# QuardnoShield_0_1.net
KiCad netlist of a schematic drawn in Altium Designer
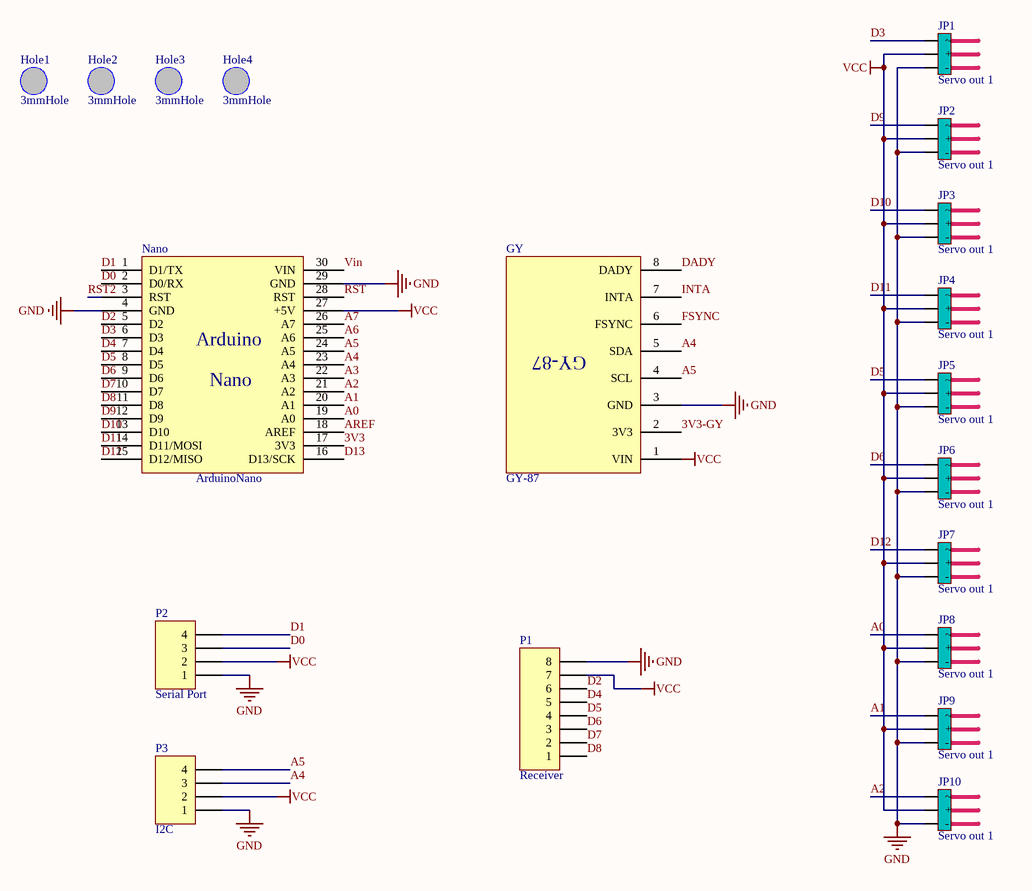
[diagram p0: QuardnoShield_0_1.SchDoc]

(export (version "E")
  (design (tool "Eeschema 10.0.6"))
  (components
    (comp (ref "GY") (value "GY-87") (footprint "GY-87") (libsource (lib "Drone") (part "GY-87")))
    (comp (ref "Hole1")
      (value "3mmHole")
      (footprint "3mmHoleSmall")
      (libsource (lib "Drone") (part "3mmHole"))
    )
    (comp (ref "Hole2")
      (value "3mmHole")
      (footprint "3mmHoleSmall")
      (libsource (lib "Drone") (part "3mmHole"))
    )
    (comp (ref "Hole3")
      (value "3mmHole")
      (footprint "3mmHoleSmall")
      (libsource (lib "Drone") (part "3mmHole"))
    )
    (comp (ref "Hole4")
      (value "3mmHole")
      (footprint "3mmHoleSmall")
      (libsource (lib "Drone") (part "3mmHole"))
    )
    (comp (ref "JP1")
      (value "Servo out 1")
      (footprint "JP")
      (description "Header, 3-Pin, 0.1\"")
      (fields (field (name "MANUFACTURER") "Generic Components"))
      (libsource (lib "Drone") (part "Hdr 3 Pin 0.1"))
    )
    (comp (ref "JP2")
      (value "Servo out 1")
      (footprint "JP")
      (description "Header, 3-Pin, 0.1\"")
      (fields (field (name "MANUFACTURER") "Generic Components"))
      (libsource (lib "Drone") (part "Hdr 3 Pin 0.1"))
    )
    (comp (ref "JP3")
      (value "Servo out 1")
      (footprint "JP")
      (description "Header, 3-Pin, 0.1\"")
      (fields (field (name "MANUFACTURER") "Generic Components"))
      (libsource (lib "Drone") (part "Hdr 3 Pin 0.1"))
    )
    (comp (ref "JP4")
      (value "Servo out 1")
      (footprint "JP")
      (description "Header, 3-Pin, 0.1\"")
      (fields (field (name "MANUFACTURER") "Generic Components"))
      (libsource (lib "Drone") (part "Hdr 3 Pin 0.1"))
    )
    (comp (ref "JP5")
      (value "Servo out 1")
      (footprint "JP")
      (description "Header, 3-Pin, 0.1\"")
      (fields (field (name "MANUFACTURER") "Generic Components"))
      (libsource (lib "Drone") (part "Hdr 3 Pin 0.1"))
    )
    (comp (ref "JP6")
      (value "Servo out 1")
      (footprint "JP")
      (description "Header, 3-Pin, 0.1\"")
      (fields (field (name "MANUFACTURER") "Generic Components"))
      (libsource (lib "Drone") (part "Hdr 3 Pin 0.1"))
    )
    (comp (ref "JP7")
      (value "Servo out 1")
      (footprint "JP")
      (description "Header, 3-Pin, 0.1\"")
      (fields (field (name "MANUFACTURER") "Generic Components"))
      (libsource (lib "Drone") (part "Hdr 3 Pin 0.1"))
    )
    (comp (ref "JP8")
      (value "Servo out 1")
      (footprint "JP")
      (description "Header, 3-Pin, 0.1\"")
      (fields (field (name "MANUFACTURER") "Generic Components"))
      (libsource (lib "Drone") (part "Hdr 3 Pin 0.1"))
    )
    (comp (ref "JP9")
      (value "Servo out 1")
      (footprint "JP")
      (description "Header, 3-Pin, 0.1\"")
      (fields (field (name "MANUFACTURER") "Generic Components"))
      (libsource (lib "Drone") (part "Hdr 3 Pin 0.1"))
    )
    (comp (ref "JP10")
      (value "Servo out 1")
      (footprint "JP")
      (description "Header, 3-Pin, 0.1\"")
      (fields (field (name "MANUFACTURER") "Generic Components"))
      (libsource (lib "Drone") (part "Hdr 3 Pin 0.1"))
    )
    (comp (ref "Nano")
      (value "ArduinoNano")
      (footprint "NanoBase")
      (libsource (lib "Drone") (part "ArduinoNano"))
    )
    (comp (ref "P1")
      (value "Receiver")
      (footprint "HDR1X8")
      (description "Header, 8-Pin")
      (fields (field (name "PUBLISHER") "Altium Limited"))
      (libsource (lib "Miscellaneous Connectors") (part "Header 8"))
    )
    (comp (ref "P2")
      (value "Serial Port")
      (footprint "HDR1X4")
      (description "Header, 4-Pin")
      (fields (field (name "PUBLISHER") "Altium Limited"))
      (libsource (lib "Miscellaneous Connectors") (part "Header 4"))
    )
    (comp (ref "P3")
      (value "I2C")
      (footprint "HDR1X4")
      (description "Header, 4-Pin")
      (fields (field (name "PUBLISHER") "Altium Limited"))
      (libsource (lib "Miscellaneous Connectors") (part "Header 4"))
    )
  )
  (nets
    (net (code "1") (name "/3V3") (class "Default")
      (node (ref "Nano") (pin "17") (pinfunction "3V3_17") (pintype "passive"))
    )
    (net (code "2") (name "/3V3-GY") (class "Default")
      (node (ref "GY") (pin "2") (pinfunction "3V3_2") (pintype "passive"))
    )
    (net (code "3") (name "/A0") (class "Default")
      (node (ref "JP8") (pin "1") (pinfunction "~_1") (pintype "passive"))
      (node (ref "Nano") (pin "19") (pinfunction "A0_19") (pintype "passive"))
    )
    (net (code "4") (name "/A1") (class "Default")
      (node (ref "JP9") (pin "1") (pinfunction "~_1") (pintype "passive"))
      (node (ref "Nano") (pin "20") (pinfunction "A1_20") (pintype "passive"))
    )
    (net (code "5") (name "/A2") (class "Default")
      (node (ref "JP10") (pin "1") (pinfunction "~_1") (pintype "passive"))
      (node (ref "Nano") (pin "21") (pinfunction "A2_21") (pintype "passive"))
    )
    (net (code "6") (name "/A3") (class "Default")
      (node (ref "Nano") (pin "22") (pinfunction "A3_22") (pintype "passive"))
    )
    (net (code "7") (name "/A4") (class "Default")
      (node (ref "GY") (pin "5") (pinfunction "SDA_5") (pintype "passive"))
      (node (ref "Nano") (pin "23") (pinfunction "A4_23") (pintype "passive"))
      (node (ref "P3") (pin "3") (pinfunction "3_3") (pintype "passive"))
    )
    (net (code "8") (name "/A5") (class "Default")
      (node (ref "GY") (pin "4") (pinfunction "SCL_4") (pintype "passive"))
      (node (ref "Nano") (pin "24") (pinfunction "A5_24") (pintype "passive"))
      (node (ref "P3") (pin "4") (pinfunction "4_4") (pintype "passive"))
    )
    (net (code "9") (name "/A6") (class "Default")
      (node (ref "Nano") (pin "25") (pinfunction "A6_25") (pintype "passive"))
    )
    (net (code "10") (name "/A7") (class "Default")
      (node (ref "Nano") (pin "26") (pinfunction "A7_26") (pintype "passive"))
    )
    (net (code "11") (name "/AREF") (class "Default")
      (node (ref "Nano") (pin "18") (pinfunction "AREF_18") (pintype "passive"))
    )
    (net (code "12") (name "/D0") (class "Default")
      (node (ref "Nano") (pin "2") (pinfunction "D0/RX_2") (pintype "passive"))
      (node (ref "P2") (pin "3") (pinfunction "3_3") (pintype "passive"))
    )
    (net (code "13") (name "/D1") (class "Default")
      (node (ref "Nano") (pin "1") (pinfunction "D1/TX_1") (pintype "passive"))
      (node (ref "P2") (pin "4") (pinfunction "4_4") (pintype "passive"))
    )
    (net (code "14") (name "/D2") (class "Default")
      (node (ref "Nano") (pin "5") (pinfunction "D2_5") (pintype "passive"))
      (node (ref "P1") (pin "6") (pinfunction "6_6") (pintype "passive"))
    )
    (net (code "15") (name "/D3") (class "Default")
      (node (ref "JP1") (pin "1") (pinfunction "~_1") (pintype "passive"))
      (node (ref "Nano") (pin "6") (pinfunction "D3_6") (pintype "passive"))
    )
    (net (code "16") (name "/D4") (class "Default")
      (node (ref "Nano") (pin "7") (pinfunction "D4_7") (pintype "passive"))
      (node (ref "P1") (pin "5") (pinfunction "5_5") (pintype "passive"))
    )
    (net (code "17") (name "/D5") (class "Default")
      (node (ref "JP5") (pin "1") (pinfunction "~_1") (pintype "passive"))
      (node (ref "Nano") (pin "8") (pinfunction "D5_8") (pintype "passive"))
      (node (ref "P1") (pin "4") (pinfunction "4_4") (pintype "passive"))
    )
    (net (code "18") (name "/D6") (class "Default")
      (node (ref "JP6") (pin "1") (pinfunction "~_1") (pintype "passive"))
      (node (ref "Nano") (pin "9") (pinfunction "D6_9") (pintype "passive"))
      (node (ref "P1") (pin "3") (pinfunction "3_3") (pintype "passive"))
    )
    (net (code "19") (name "/D7") (class "Default")
      (node (ref "Nano") (pin "10") (pinfunction "D7_10") (pintype "passive"))
      (node (ref "P1") (pin "2") (pinfunction "2_2") (pintype "passive"))
    )
    (net (code "20") (name "/D8") (class "Default")
      (node (ref "Nano") (pin "11") (pinfunction "D8_11") (pintype "passive"))
      (node (ref "P1") (pin "1") (pinfunction "1_1") (pintype "passive"))
    )
    (net (code "21") (name "/D9") (class "Default")
      (node (ref "JP2") (pin "1") (pinfunction "~_1") (pintype "passive"))
      (node (ref "Nano") (pin "12") (pinfunction "D9_12") (pintype "passive"))
    )
    (net (code "22") (name "/D10") (class "Default")
      (node (ref "JP3") (pin "1") (pinfunction "~_1") (pintype "passive"))
      (node (ref "Nano") (pin "13") (pinfunction "D10_13") (pintype "passive"))
    )
    (net (code "23") (name "/D11") (class "Default")
      (node (ref "JP4") (pin "1") (pinfunction "~_1") (pintype "passive"))
      (node (ref "Nano") (pin "14") (pinfunction "D11/MOSI_14") (pintype "passive"))
    )
    (net (code "24") (name "/D12") (class "Default")
      (node (ref "JP7") (pin "1") (pinfunction "~_1") (pintype "passive"))
      (node (ref "Nano") (pin "15") (pinfunction "D12/MISO_15") (pintype "passive"))
    )
    (net (code "25") (name "/D13") (class "Default")
      (node (ref "Nano") (pin "16") (pinfunction "D13/SCK_16") (pintype "passive"))
    )
    (net (code "26") (name "/DADY") (class "Default")
      (node (ref "GY") (pin "8") (pinfunction "DADY_8") (pintype "passive"))
    )
    (net (code "27") (name "/FSYNC") (class "Default")
      (node (ref "GY") (pin "6") (pinfunction "FSYNC_6") (pintype "passive"))
    )
    (net (code "28") (name "/INTA") (class "Default")
      (node (ref "GY") (pin "7") (pinfunction "INTA_7") (pintype "passive"))
    )
    (net (code "29") (name "/RST") (class "Default")
      (node (ref "Nano") (pin "28") (pinfunction "RST_28") (pintype "passive"))
    )
    (net (code "30") (name "/RST2") (class "Default")
      (node (ref "Nano") (pin "3") (pinfunction "RST_3") (pintype "passive"))
    )
    (net (code "31") (name "/Vin") (class "Default")
      (node (ref "Nano") (pin "30") (pinfunction "VIN_30") (pintype "passive"))
    )
    (net (code "32") (name "GND") (class "Default")
      (node (ref "GY") (pin "3") (pinfunction "GND_3") (pintype "passive"))
      (node (ref "JP1") (pin "3") (pinfunction "-_3") (pintype "passive"))
      (node (ref "JP10") (pin "3") (pinfunction "-_3") (pintype "passive"))
      (node (ref "JP2") (pin "3") (pinfunction "-_3") (pintype "passive"))
      (node (ref "JP3") (pin "3") (pinfunction "-_3") (pintype "passive"))
      (node (ref "JP4") (pin "3") (pinfunction "-_3") (pintype "passive"))
      (node (ref "JP5") (pin "3") (pinfunction "-_3") (pintype "passive"))
      (node (ref "JP6") (pin "3") (pinfunction "-_3") (pintype "passive"))
      (node (ref "JP7") (pin "3") (pinfunction "-_3") (pintype "passive"))
      (node (ref "JP8") (pin "3") (pinfunction "-_3") (pintype "passive"))
      (node (ref "JP9") (pin "3") (pinfunction "-_3") (pintype "passive"))
      (node (ref "Nano") (pin "29") (pinfunction "GND_29") (pintype "passive"))
      (node (ref "Nano") (pin "4") (pinfunction "GND_4") (pintype "passive"))
      (node (ref "P1") (pin "8") (pinfunction "8_8") (pintype "passive"))
      (node (ref "P2") (pin "1") (pinfunction "1_1") (pintype "passive"))
      (node (ref "P3") (pin "1") (pinfunction "1_1") (pintype "passive"))
    )
    (net (code "33") (name "VCC") (class "Default")
      (node (ref "GY") (pin "1") (pinfunction "VIN_1") (pintype "passive"))
      (node (ref "JP1") (pin "2") (pinfunction "+_2") (pintype "passive"))
      (node (ref "JP10") (pin "2") (pinfunction "+_2") (pintype "passive"))
      (node (ref "JP2") (pin "2") (pinfunction "+_2") (pintype "passive"))
      (node (ref "JP3") (pin "2") (pinfunction "+_2") (pintype "passive"))
      (node (ref "JP4") (pin "2") (pinfunction "+_2") (pintype "passive"))
      (node (ref "JP5") (pin "2") (pinfunction "+_2") (pintype "passive"))
      (node (ref "JP6") (pin "2") (pinfunction "+_2") (pintype "passive"))
      (node (ref "JP7") (pin "2") (pinfunction "+_2") (pintype "passive"))
      (node (ref "JP8") (pin "2") (pinfunction "+_2") (pintype "passive"))
      (node (ref "JP9") (pin "2") (pinfunction "+_2") (pintype "passive"))
      (node (ref "Nano") (pin "27") (pinfunction "+5V_27") (pintype "passive"))
      (node (ref "P1") (pin "7") (pinfunction "7_7") (pintype "passive"))
      (node (ref "P2") (pin "2") (pinfunction "2_2") (pintype "passive"))
      (node (ref "P3") (pin "2") (pinfunction "2_2") (pintype "passive"))
    )
  )
)
